# CanBus-Forward.net
KiCad netlist of a schematic drawn in EAGLE
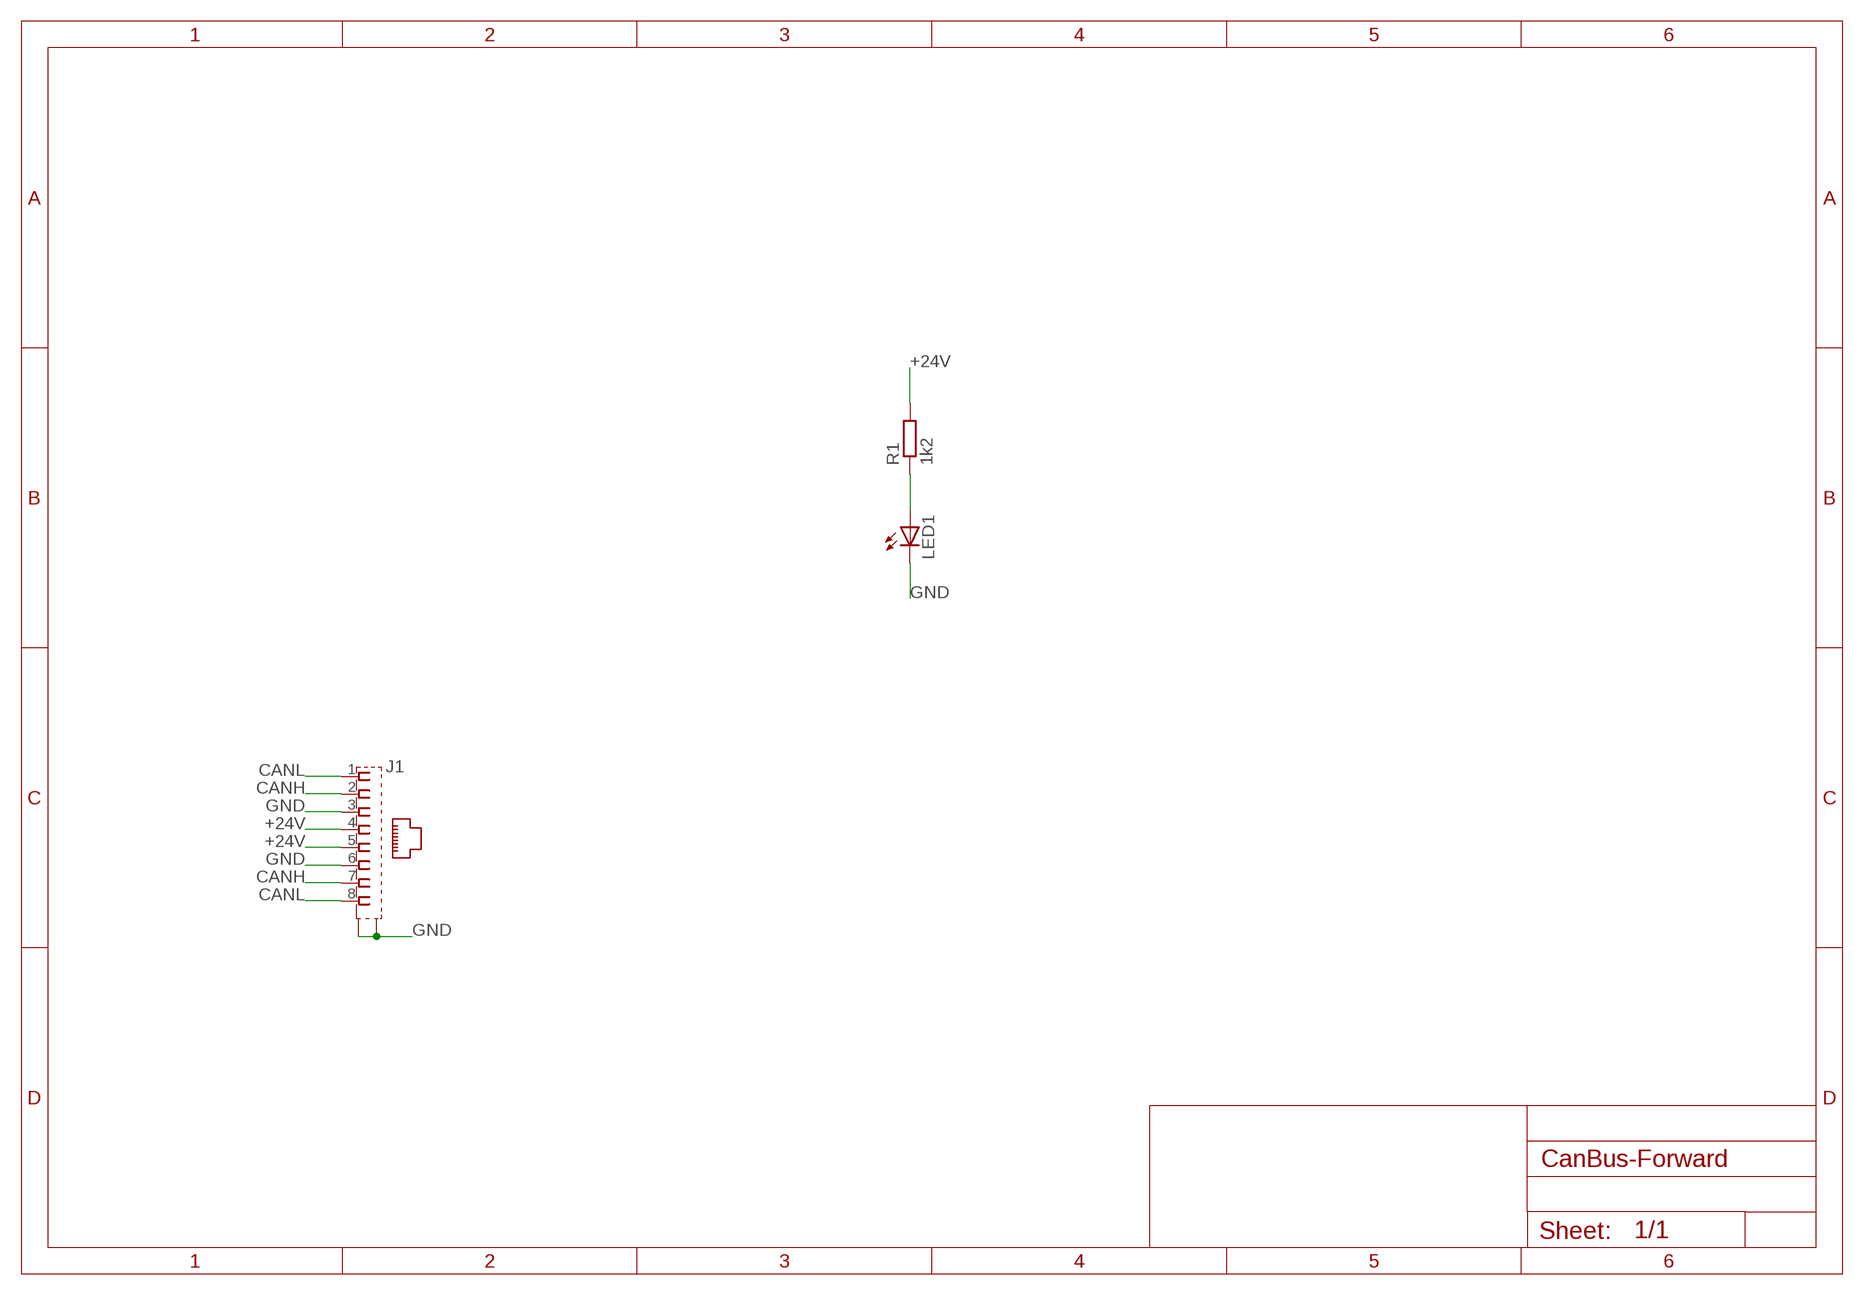
[diagram p0: schematic, sheet 1]

(export (version "E")
  (design (tool "Eeschema 10.0.6"))
  (components
    (comp (ref "J1")
      (value "555141-1")
      (footprint "eagle-import:MEBP_8-8G")
      (libsource (lib "eagle-import") (part "555141-1"))
    )
    (comp (ref "LED1")
      (value "LEDCHIPLED_1206")
      (footprint "eagle-import:CHIPLED_1206")
      (libsource (lib "eagle-import") (part "LEDCHIPLED_1206"))
    )
    (comp (ref "R1")
      (value "1k2")
      (footprint "eagle-import:R1206")
      (libsource (lib "eagle-import") (part "R-EU_R1206"))
    )
  )
  (nets
    (net (code "1") (name "/+24V") (class "Default")
      (node (ref "J1") (pin "4") (pinfunction "4_4") (pintype "passive"))
      (node (ref "J1") (pin "5") (pinfunction "5_5") (pintype "passive"))
      (node (ref "R1") (pin "2") (pinfunction "2_2") (pintype "passive"))
    )
    (net (code "2") (name "/CANH") (class "Default")
      (node (ref "J1") (pin "2") (pinfunction "2_2") (pintype "passive"))
      (node (ref "J1") (pin "7") (pinfunction "7_7") (pintype "passive"))
    )
    (net (code "3") (name "/CANL") (class "Default")
      (node (ref "J1") (pin "1") (pinfunction "1_1") (pintype "passive"))
      (node (ref "J1") (pin "8") (pinfunction "8_8") (pintype "passive"))
    )
    (net (code "4") (name "/GND") (class "Default")
      (node (ref "J1") (pin "3") (pinfunction "3_3") (pintype "passive"))
      (node (ref "J1") (pin "6") (pinfunction "6_6") (pintype "passive"))
      (node (ref "J1") (pin "G1") (pinfunction "S1_G1") (pintype "passive"))
      (node (ref "J1") (pin "G2") (pinfunction "S2_G2") (pintype "passive"))
      (node (ref "LED1") (pin "C") (pinfunction "C_C") (pintype "passive"))
    )
    (net (code "5") (name "Net-(LED1-PadA)") (class "Default")
      (node (ref "LED1") (pin "A") (pinfunction "A_A") (pintype "passive"))
      (node (ref "R1") (pin "1") (pinfunction "1_1") (pintype "passive"))
    )
  )
)
